# Decoupling_CAP.net
KiCad netlist of a schematic drawn in Altium Designer
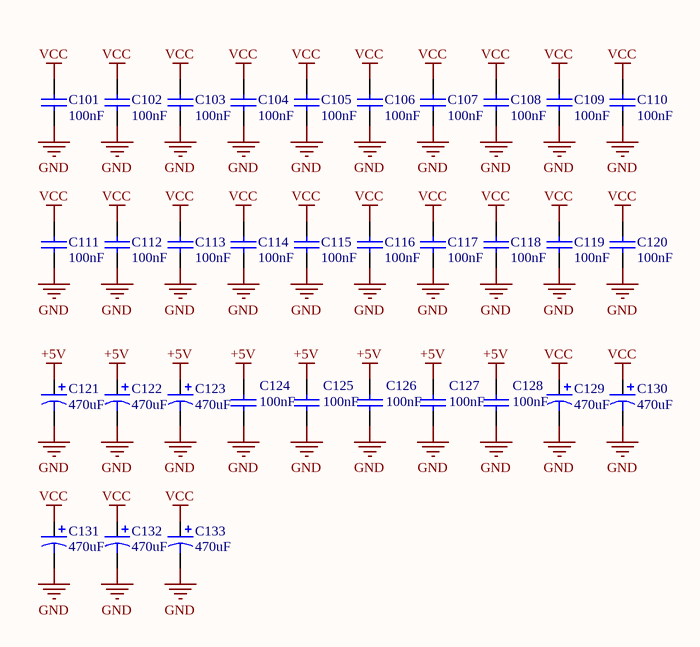
[diagram p0: Decoupling CAP.SchDoc]

(export (version "E")
  (design (tool "Eeschema 10.0.6"))
  (components
    (comp (ref "C101")
      (value "100nF")
      (footprint "CAPC0603(1608)55_M")
      (libsource (lib "Slivy's ibrary") (part "CAP"))
    )
    (comp (ref "C102")
      (value "100nF")
      (footprint "CAPC0603(1608)55_M")
      (libsource (lib "Slivy's ibrary") (part "CAP"))
    )
    (comp (ref "C103")
      (value "100nF")
      (footprint "CAPC0603(1608)55_M")
      (libsource (lib "Slivy's ibrary") (part "CAP"))
    )
    (comp (ref "C104")
      (value "100nF")
      (footprint "CAPC0603(1608)55_M")
      (libsource (lib "Slivy's ibrary") (part "CAP"))
    )
    (comp (ref "C105")
      (value "100nF")
      (footprint "CAPC0603(1608)55_M")
      (libsource (lib "Slivy's ibrary") (part "CAP"))
    )
    (comp (ref "C106")
      (value "100nF")
      (footprint "CAPC0603(1608)55_M")
      (libsource (lib "Slivy's ibrary") (part "CAP"))
    )
    (comp (ref "C107")
      (value "100nF")
      (footprint "CAPC0603(1608)55_M")
      (libsource (lib "Slivy's ibrary") (part "CAP"))
    )
    (comp (ref "C108")
      (value "100nF")
      (footprint "CAPC0603(1608)55_M")
      (libsource (lib "Slivy's ibrary") (part "CAP"))
    )
    (comp (ref "C109")
      (value "100nF")
      (footprint "CAPC0603(1608)55_M")
      (libsource (lib "Slivy's ibrary") (part "CAP"))
    )
    (comp (ref "C110")
      (value "100nF")
      (footprint "CAPC0603(1608)55_M")
      (libsource (lib "Slivy's ibrary") (part "CAP"))
    )
    (comp (ref "C111")
      (value "100nF")
      (footprint "CAPC0603(1608)55_M")
      (libsource (lib "Slivy's ibrary") (part "CAP"))
    )
    (comp (ref "C112")
      (value "100nF")
      (footprint "CAPC0603(1608)55_M")
      (libsource (lib "Slivy's ibrary") (part "CAP"))
    )
    (comp (ref "C113")
      (value "100nF")
      (footprint "CAPC0603(1608)55_M")
      (libsource (lib "Slivy's ibrary") (part "CAP"))
    )
    (comp (ref "C114")
      (value "100nF")
      (footprint "CAPC0603(1608)55_M")
      (libsource (lib "Slivy's ibrary") (part "CAP"))
    )
    (comp (ref "C115")
      (value "100nF")
      (footprint "CAPC0603(1608)55_M")
      (libsource (lib "Slivy's ibrary") (part "CAP"))
    )
    (comp (ref "C116")
      (value "100nF")
      (footprint "CAPC0603(1608)55_M")
      (libsource (lib "Slivy's ibrary") (part "CAP"))
    )
    (comp (ref "C117")
      (value "100nF")
      (footprint "CAPC0603(1608)55_M")
      (libsource (lib "Slivy's ibrary") (part "CAP"))
    )
    (comp (ref "C118")
      (value "100nF")
      (footprint "CAPC0603(1608)55_M")
      (libsource (lib "Slivy's ibrary") (part "CAP"))
    )
    (comp (ref "C119")
      (value "100nF")
      (footprint "CAPC0603(1608)55_M")
      (libsource (lib "Slivy's ibrary") (part "CAP"))
    )
    (comp (ref "C120")
      (value "100nF")
      (footprint "CAPC0603(1608)55_M")
      (libsource (lib "Slivy's ibrary") (part "CAP"))
    )
    (comp (ref "C121")
      (value "470uF")
      (footprint "CAPC7343")
      (libsource (lib "Slivy's ibrary") (part "CAP-Pol"))
    )
    (comp (ref "C122")
      (value "470uF")
      (footprint "CAPC7343")
      (libsource (lib "Slivy's ibrary") (part "CAP-Pol"))
    )
    (comp (ref "C123")
      (value "470uF")
      (footprint "CAPC7343")
      (libsource (lib "Slivy's ibrary") (part "CAP-Pol"))
    )
    (comp (ref "C124")
      (value "100nF")
      (footprint "CAPC0603(1608)55_M")
      (libsource (lib "Slivy's ibrary") (part "CAP"))
    )
    (comp (ref "C125")
      (value "100nF")
      (footprint "CAPC0603(1608)55_M")
      (libsource (lib "Slivy's ibrary") (part "CAP"))
    )
    (comp (ref "C126")
      (value "100nF")
      (footprint "CAPC0603(1608)55_M")
      (libsource (lib "Slivy's ibrary") (part "CAP"))
    )
    (comp (ref "C127")
      (value "100nF")
      (footprint "CAPC0603(1608)55_M")
      (libsource (lib "Slivy's ibrary") (part "CAP"))
    )
    (comp (ref "C128")
      (value "100nF")
      (footprint "CAPC0603(1608)55_M")
      (libsource (lib "Slivy's ibrary") (part "CAP"))
    )
    (comp (ref "C129")
      (value "470uF")
      (footprint "CAPC7343")
      (libsource (lib "Slivy's ibrary") (part "CAP-Pol"))
    )
    (comp (ref "C130")
      (value "470uF")
      (footprint "CAPC7343")
      (libsource (lib "Slivy's ibrary") (part "CAP-Pol"))
    )
    (comp (ref "C131")
      (value "470uF")
      (footprint "CAPC7343")
      (libsource (lib "Slivy's ibrary") (part "CAP-Pol"))
    )
    (comp (ref "C132")
      (value "470uF")
      (footprint "CAPC7343")
      (libsource (lib "Slivy's ibrary") (part "CAP-Pol"))
    )
    (comp (ref "C133")
      (value "470uF")
      (footprint "CAPC7343")
      (libsource (lib "Slivy's ibrary") (part "CAP-Pol"))
    )
  )
  (nets
    (net (code "1") (name "+5V") (class "Default")
      (node (ref "C121") (pin "1") (pinfunction "1_1") (pintype "passive"))
      (node (ref "C122") (pin "1") (pinfunction "1_1") (pintype "passive"))
      (node (ref "C123") (pin "1") (pinfunction "1_1") (pintype "passive"))
      (node (ref "C124") (pin "2") (pinfunction "2_2") (pintype "passive"))
      (node (ref "C125") (pin "2") (pinfunction "2_2") (pintype "passive"))
      (node (ref "C126") (pin "2") (pinfunction "2_2") (pintype "passive"))
      (node (ref "C127") (pin "2") (pinfunction "2_2") (pintype "passive"))
      (node (ref "C128") (pin "2") (pinfunction "2_2") (pintype "passive"))
    )
    (net (code "2") (name "GND") (class "Default")
      (node (ref "C101") (pin "1") (pinfunction "1_1") (pintype "passive"))
      (node (ref "C102") (pin "1") (pinfunction "1_1") (pintype "passive"))
      (node (ref "C103") (pin "1") (pinfunction "1_1") (pintype "passive"))
      (node (ref "C104") (pin "1") (pinfunction "1_1") (pintype "passive"))
      (node (ref "C105") (pin "1") (pinfunction "1_1") (pintype "passive"))
      (node (ref "C106") (pin "1") (pinfunction "1_1") (pintype "passive"))
      (node (ref "C107") (pin "1") (pinfunction "1_1") (pintype "passive"))
      (node (ref "C108") (pin "1") (pinfunction "1_1") (pintype "passive"))
      (node (ref "C109") (pin "1") (pinfunction "1_1") (pintype "passive"))
      (node (ref "C110") (pin "1") (pinfunction "1_1") (pintype "passive"))
      (node (ref "C111") (pin "1") (pinfunction "1_1") (pintype "passive"))
      (node (ref "C112") (pin "1") (pinfunction "1_1") (pintype "passive"))
      (node (ref "C113") (pin "1") (pinfunction "1_1") (pintype "passive"))
      (node (ref "C114") (pin "1") (pinfunction "1_1") (pintype "passive"))
      (node (ref "C115") (pin "1") (pinfunction "1_1") (pintype "passive"))
      (node (ref "C116") (pin "1") (pinfunction "1_1") (pintype "passive"))
      (node (ref "C117") (pin "1") (pinfunction "1_1") (pintype "passive"))
      (node (ref "C118") (pin "1") (pinfunction "1_1") (pintype "passive"))
      (node (ref "C119") (pin "1") (pinfunction "1_1") (pintype "passive"))
      (node (ref "C120") (pin "1") (pinfunction "1_1") (pintype "passive"))
      (node (ref "C121") (pin "2") (pinfunction "2_2") (pintype "passive"))
      (node (ref "C122") (pin "2") (pinfunction "2_2") (pintype "passive"))
      (node (ref "C123") (pin "2") (pinfunction "2_2") (pintype "passive"))
      (node (ref "C124") (pin "1") (pinfunction "1_1") (pintype "passive"))
      (node (ref "C125") (pin "1") (pinfunction "1_1") (pintype "passive"))
      (node (ref "C126") (pin "1") (pinfunction "1_1") (pintype "passive"))
      (node (ref "C127") (pin "1") (pinfunction "1_1") (pintype "passive"))
      (node (ref "C128") (pin "1") (pinfunction "1_1") (pintype "passive"))
      (node (ref "C129") (pin "2") (pinfunction "2_2") (pintype "passive"))
      (node (ref "C130") (pin "2") (pinfunction "2_2") (pintype "passive"))
      (node (ref "C131") (pin "2") (pinfunction "2_2") (pintype "passive"))
      (node (ref "C132") (pin "2") (pinfunction "2_2") (pintype "passive"))
      (node (ref "C133") (pin "2") (pinfunction "2_2") (pintype "passive"))
    )
    (net (code "3") (name "VCC") (class "Default")
      (node (ref "C101") (pin "2") (pinfunction "2_2") (pintype "passive"))
      (node (ref "C102") (pin "2") (pinfunction "2_2") (pintype "passive"))
      (node (ref "C103") (pin "2") (pinfunction "2_2") (pintype "passive"))
      (node (ref "C104") (pin "2") (pinfunction "2_2") (pintype "passive"))
      (node (ref "C105") (pin "2") (pinfunction "2_2") (pintype "passive"))
      (node (ref "C106") (pin "2") (pinfunction "2_2") (pintype "passive"))
      (node (ref "C107") (pin "2") (pinfunction "2_2") (pintype "passive"))
      (node (ref "C108") (pin "2") (pinfunction "2_2") (pintype "passive"))
      (node (ref "C109") (pin "2") (pinfunction "2_2") (pintype "passive"))
      (node (ref "C110") (pin "2") (pinfunction "2_2") (pintype "passive"))
      (node (ref "C111") (pin "2") (pinfunction "2_2") (pintype "passive"))
      (node (ref "C112") (pin "2") (pinfunction "2_2") (pintype "passive"))
      (node (ref "C113") (pin "2") (pinfunction "2_2") (pintype "passive"))
      (node (ref "C114") (pin "2") (pinfunction "2_2") (pintype "passive"))
      (node (ref "C115") (pin "2") (pinfunction "2_2") (pintype "passive"))
      (node (ref "C116") (pin "2") (pinfunction "2_2") (pintype "passive"))
      (node (ref "C117") (pin "2") (pinfunction "2_2") (pintype "passive"))
      (node (ref "C118") (pin "2") (pinfunction "2_2") (pintype "passive"))
      (node (ref "C119") (pin "2") (pinfunction "2_2") (pintype "passive"))
      (node (ref "C120") (pin "2") (pinfunction "2_2") (pintype "passive"))
      (node (ref "C129") (pin "1") (pinfunction "1_1") (pintype "passive"))
      (node (ref "C130") (pin "1") (pinfunction "1_1") (pintype "passive"))
      (node (ref "C131") (pin "1") (pinfunction "1_1") (pintype "passive"))
      (node (ref "C132") (pin "1") (pinfunction "1_1") (pintype "passive"))
      (node (ref "C133") (pin "1") (pinfunction "1_1") (pintype "passive"))
    )
  )
)
